# CAM.net
KiCad netlist of a schematic drawn in Altium Designer
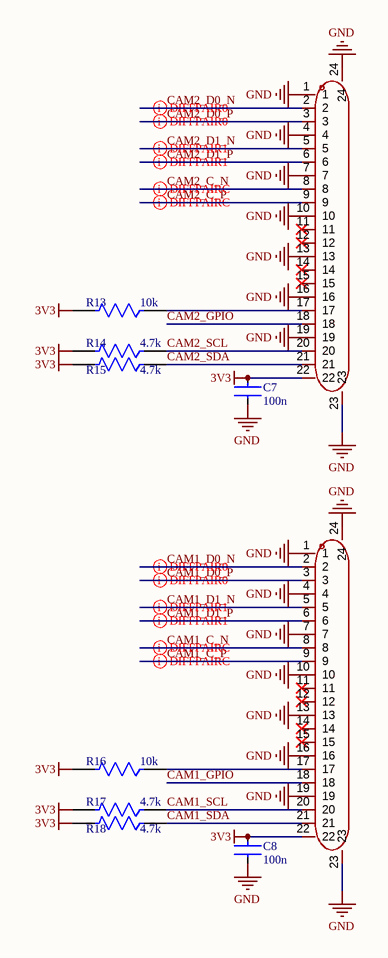
[diagram p0: CAM.SchDoc]

(export (version "E")
  (design (tool "Eeschema 10.0.6"))
  (components
    (comp (ref "C7")
      (value "100n")
      (footprint "CAP_0402")
      (description "C307331")
      (fields (field (name "TOLERANCE") "10%"))
      (libsource (lib "LEAKCAM") (part "CMP-03422-001116-1"))
    )
    (comp (ref "C8")
      (value "100n")
      (footprint "CAP_0402")
      (description "C307331")
      (fields (field (name "TOLERANCE") "10%"))
      (libsource (lib "LEAKCAM") (part "CMP-03422-001116-1"))
    )
    (comp (ref "J4")
      (value "05b20l22p")
      (footprint "FLEX_CON_22P")
      (description "C22459552")
      (fields
        (field (name "MANUFACTURER") "HanElectricity(瀚源)")
        (field (name "MANUFACTURERPART") "05B20L22P")
      )
      (libsource (lib "LEAKCAM") (part "05b20l22p"))
    )
    (comp (ref "J5")
      (value "05b20l22p")
      (footprint "FLEX_CON_22P")
      (description "C22459552")
      (fields
        (field (name "MANUFACTURER") "HanElectricity(瀚源)")
        (field (name "MANUFACTURERPART") "05B20L22P")
      )
      (libsource (lib "LEAKCAM") (part "05b20l22p"))
    )
    (comp (ref "R13")
      (value "10k")
      (footprint "RES_0402")
      (description "C25744")
      (fields (field (name "TOLERANCE") "1%"))
      (libsource (lib "LEAKCAM") (part "CMP-03412-016018-1"))
    )
    (comp (ref "R14")
      (value "4.7k")
      (footprint "RES_0402")
      (description "C25900")
      (fields (field (name "TOLERANCE") "1%"))
      (libsource (lib "LEAKCAM") (part "CMP-03412-016018-1"))
    )
    (comp (ref "R15")
      (value "4.7k")
      (footprint "RES_0402")
      (description "C25900")
      (fields (field (name "TOLERANCE") "1%"))
      (libsource (lib "LEAKCAM") (part "CMP-03412-016018-1"))
    )
    (comp (ref "R16")
      (value "10k")
      (footprint "RES_0402")
      (description "C25744")
      (fields (field (name "TOLERANCE") "1%"))
      (libsource (lib "LEAKCAM") (part "CMP-03412-016018-1"))
    )
    (comp (ref "R17")
      (value "4.7k")
      (footprint "RES_0402")
      (description "C25900")
      (fields (field (name "TOLERANCE") "1%"))
      (libsource (lib "LEAKCAM") (part "CMP-03412-016018-1"))
    )
    (comp (ref "R18")
      (value "4.7k")
      (footprint "RES_0402")
      (description "C25900")
      (fields (field (name "TOLERANCE") "1%"))
      (libsource (lib "LEAKCAM") (part "CMP-03412-016018-1"))
    )
  )
  (nets
    (net (code "1") (name "/CAM1_C_N") (class "Default")
      (node (ref "J5") (pin "8") (pinfunction "8_8") (pintype "passive"))
    )
    (net (code "2") (name "/CAM1_C_P") (class "Default")
      (node (ref "J5") (pin "9") (pinfunction "9_9") (pintype "passive"))
    )
    (net (code "3") (name "/CAM1_D0_N") (class "Default")
      (node (ref "J5") (pin "2") (pinfunction "2_2") (pintype "passive"))
    )
    (net (code "4") (name "/CAM1_D0_P") (class "Default")
      (node (ref "J5") (pin "3") (pinfunction "3_3") (pintype "passive"))
    )
    (net (code "5") (name "/CAM1_D1_N") (class "Default")
      (node (ref "J5") (pin "5") (pinfunction "5_5") (pintype "passive"))
    )
    (net (code "6") (name "/CAM1_D1_P") (class "Default")
      (node (ref "J5") (pin "6") (pinfunction "6_6") (pintype "passive"))
    )
    (net (code "7") (name "/CAM1_GPIO") (class "Default")
      (node (ref "J5") (pin "18") (pinfunction "18_18") (pintype "passive"))
    )
    (net (code "8") (name "/CAM1_SCL") (class "Default")
      (node (ref "J5") (pin "20") (pinfunction "20_20") (pintype "passive"))
      (node (ref "R17") (pin "1") (pinfunction "1_1") (pintype "passive"))
    )
    (net (code "9") (name "/CAM1_SDA") (class "Default")
      (node (ref "J5") (pin "21") (pinfunction "21_21") (pintype "passive"))
      (node (ref "R18") (pin "1") (pinfunction "1_1") (pintype "passive"))
    )
    (net (code "10") (name "/CAM2_C_N") (class "Default")
      (node (ref "J4") (pin "8") (pinfunction "8_8") (pintype "passive"))
    )
    (net (code "11") (name "/CAM2_C_P") (class "Default")
      (node (ref "J4") (pin "9") (pinfunction "9_9") (pintype "passive"))
    )
    (net (code "12") (name "/CAM2_D0_N") (class "Default")
      (node (ref "J4") (pin "2") (pinfunction "2_2") (pintype "passive"))
    )
    (net (code "13") (name "/CAM2_D0_P") (class "Default")
      (node (ref "J4") (pin "3") (pinfunction "3_3") (pintype "passive"))
    )
    (net (code "14") (name "/CAM2_D1_N") (class "Default")
      (node (ref "J4") (pin "5") (pinfunction "5_5") (pintype "passive"))
    )
    (net (code "15") (name "/CAM2_D1_P") (class "Default")
      (node (ref "J4") (pin "6") (pinfunction "6_6") (pintype "passive"))
    )
    (net (code "16") (name "/CAM2_GPIO") (class "Default")
      (node (ref "J4") (pin "18") (pinfunction "18_18") (pintype "passive"))
    )
    (net (code "17") (name "/CAM2_SCL") (class "Default")
      (node (ref "J4") (pin "20") (pinfunction "20_20") (pintype "passive"))
      (node (ref "R14") (pin "1") (pinfunction "1_1") (pintype "passive"))
    )
    (net (code "18") (name "/CAM2_SDA") (class "Default")
      (node (ref "J4") (pin "21") (pinfunction "21_21") (pintype "passive"))
      (node (ref "R15") (pin "1") (pinfunction "1_1") (pintype "passive"))
    )
    (net (code "19") (name "3V3") (class "Default")
      (node (ref "C7") (pin "1") (pinfunction "1_1") (pintype "passive"))
      (node (ref "C8") (pin "1") (pinfunction "1_1") (pintype "passive"))
      (node (ref "J4") (pin "22") (pinfunction "22_22") (pintype "passive"))
      (node (ref "J5") (pin "22") (pinfunction "22_22") (pintype "passive"))
      (node (ref "R13") (pin "2") (pinfunction "2_2") (pintype "passive"))
      (node (ref "R14") (pin "2") (pinfunction "2_2") (pintype "passive"))
      (node (ref "R15") (pin "2") (pinfunction "2_2") (pintype "passive"))
      (node (ref "R16") (pin "2") (pinfunction "2_2") (pintype "passive"))
      (node (ref "R17") (pin "2") (pinfunction "2_2") (pintype "passive"))
      (node (ref "R18") (pin "2") (pinfunction "2_2") (pintype "passive"))
    )
    (net (code "20") (name "GND") (class "Default")
      (node (ref "C7") (pin "2") (pinfunction "2_2") (pintype "passive"))
      (node (ref "C8") (pin "2") (pinfunction "2_2") (pintype "passive"))
      (node (ref "J4") (pin "1") (pinfunction "1_1") (pintype "passive"))
      (node (ref "J4") (pin "10") (pinfunction "10_10") (pintype "passive"))
      (node (ref "J4") (pin "13") (pinfunction "13_13") (pintype "passive"))
      (node (ref "J4") (pin "16") (pinfunction "16_16") (pintype "passive"))
      (node (ref "J4") (pin "19") (pinfunction "19_19") (pintype "passive"))
      (node (ref "J4") (pin "23") (pinfunction "23_23") (pintype "passive"))
      (node (ref "J4") (pin "24") (pinfunction "24_24") (pintype "passive"))
      (node (ref "J4") (pin "4") (pinfunction "4_4") (pintype "passive"))
      (node (ref "J4") (pin "7") (pinfunction "7_7") (pintype "passive"))
      (node (ref "J5") (pin "1") (pinfunction "1_1") (pintype "passive"))
      (node (ref "J5") (pin "10") (pinfunction "10_10") (pintype "passive"))
      (node (ref "J5") (pin "13") (pinfunction "13_13") (pintype "passive"))
      (node (ref "J5") (pin "16") (pinfunction "16_16") (pintype "passive"))
      (node (ref "J5") (pin "19") (pinfunction "19_19") (pintype "passive"))
      (node (ref "J5") (pin "23") (pinfunction "23_23") (pintype "passive"))
      (node (ref "J5") (pin "24") (pinfunction "24_24") (pintype "passive"))
      (node (ref "J5") (pin "4") (pinfunction "4_4") (pintype "passive"))
      (node (ref "J5") (pin "7") (pinfunction "7_7") (pintype "passive"))
    )
    (net (code "21") (name "Net-(J4-Pad17)") (class "Default")
      (node (ref "J4") (pin "17") (pinfunction "17_17") (pintype "passive"))
      (node (ref "R13") (pin "1") (pinfunction "1_1") (pintype "passive"))
    )
    (net (code "22") (name "Net-(J5-Pad17)") (class "Default")
      (node (ref "J5") (pin "17") (pinfunction "17_17") (pintype "passive"))
      (node (ref "R16") (pin "1") (pinfunction "1_1") (pintype "passive"))
    )
    (net (code "23") (name "unconnected-(J4-Pad11)") (class "Default")
      (node (ref "J4") (pin "11") (pinfunction "11_11") (pintype "passive+no_connect"))
    )
    (net (code "24") (name "unconnected-(J4-Pad12)") (class "Default")
      (node (ref "J4") (pin "12") (pinfunction "12_12") (pintype "passive+no_connect"))
    )
    (net (code "25") (name "unconnected-(J4-Pad14)") (class "Default")
      (node (ref "J4") (pin "14") (pinfunction "14_14") (pintype "passive+no_connect"))
    )
    (net (code "26") (name "unconnected-(J4-Pad15)") (class "Default")
      (node (ref "J4") (pin "15") (pinfunction "15_15") (pintype "passive+no_connect"))
    )
    (net (code "27") (name "unconnected-(J5-Pad11)") (class "Default")
      (node (ref "J5") (pin "11") (pinfunction "11_11") (pintype "passive+no_connect"))
    )
    (net (code "28") (name "unconnected-(J5-Pad12)") (class "Default")
      (node (ref "J5") (pin "12") (pinfunction "12_12") (pintype "passive+no_connect"))
    )
    (net (code "29") (name "unconnected-(J5-Pad14)") (class "Default")
      (node (ref "J5") (pin "14") (pinfunction "14_14") (pintype "passive+no_connect"))
    )
    (net (code "30") (name "unconnected-(J5-Pad15)") (class "Default")
      (node (ref "J5") (pin "15") (pinfunction "15_15") (pintype "passive+no_connect"))
    )
  )
)
